# Variometer.net
KiCad netlist of a schematic drawn in EAGLE
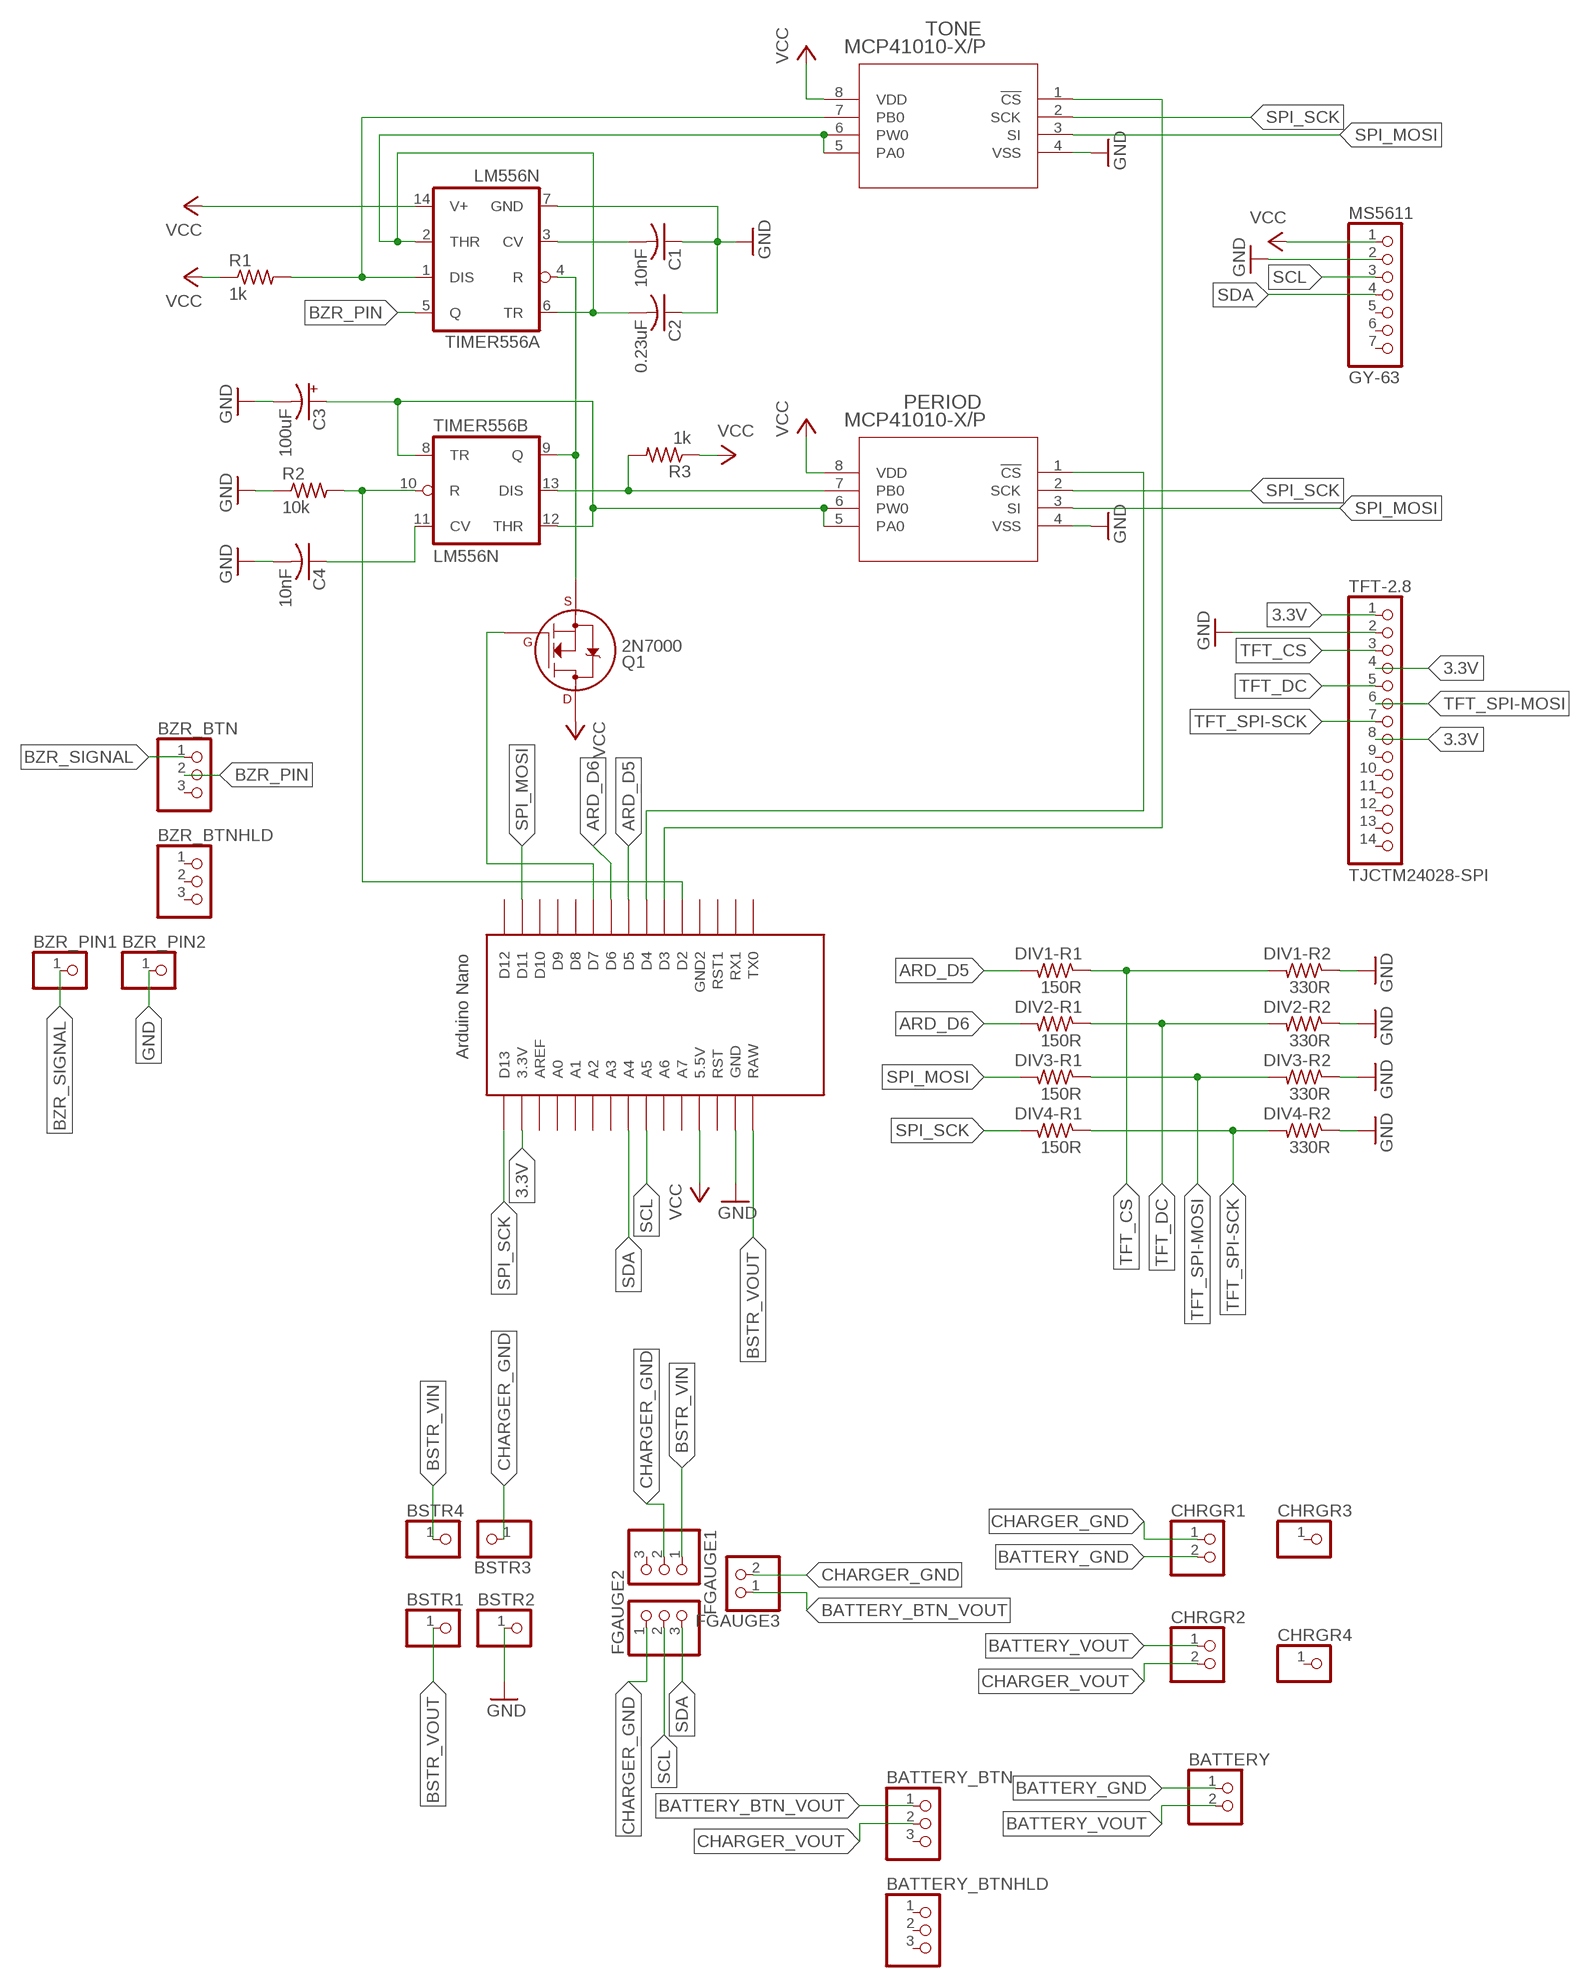
[diagram p0: schematic, sheet 1]

(export (version "E")
  (design (tool "Eeschema 10.0.6"))
  (components
    (comp (ref "BATTERY")
      (value "PINHD-1X2")
      (footprint "eagle-import:1X02")
      (libsource (lib "eagle-import") (part "PINHD-1X2"))
    )
    (comp (ref "BATTERY_BTN")
      (value "PINHD-1X3")
      (footprint "eagle-import:1X03")
      (libsource (lib "eagle-import") (part "PINHD-1X3"))
    )
    (comp (ref "BATTERY_BTNHLD")
      (value "PINHD-1X3")
      (footprint "eagle-import:1X03")
      (libsource (lib "eagle-import") (part "PINHD-1X3"))
    )
    (comp (ref "BSTR1")
      (value "PINHD-1X1")
      (footprint "eagle-import:1X01")
      (libsource (lib "eagle-import") (part "PINHD-1X1"))
    )
    (comp (ref "BSTR2")
      (value "PINHD-1X1")
      (footprint "eagle-import:1X01")
      (libsource (lib "eagle-import") (part "PINHD-1X1"))
    )
    (comp (ref "BSTR3")
      (value "PINHD-1X1")
      (footprint "eagle-import:1X01")
      (libsource (lib "eagle-import") (part "PINHD-1X1"))
    )
    (comp (ref "BSTR4")
      (value "PINHD-1X1")
      (footprint "eagle-import:1X01")
      (libsource (lib "eagle-import") (part "PINHD-1X1"))
    )
    (comp (ref "BZR_BTN")
      (value "PINHD-1X3")
      (footprint "eagle-import:1X03")
      (libsource (lib "eagle-import") (part "PINHD-1X3"))
    )
    (comp (ref "BZR_BTNHLD")
      (value "PINHD-1X3")
      (footprint "eagle-import:1X03")
      (libsource (lib "eagle-import") (part "PINHD-1X3"))
    )
    (comp (ref "BZR_PIN1")
      (value "PINHD-1X1")
      (footprint "eagle-import:1X01")
      (libsource (lib "eagle-import") (part "PINHD-1X1"))
    )
    (comp (ref "BZR_PIN2")
      (value "PINHD-1X1")
      (footprint "eagle-import:1X01")
      (libsource (lib "eagle-import") (part "PINHD-1X1"))
    )
    (comp (ref "C1")
      (value "10nF")
      (footprint "eagle-import:C025-024X044")
      (libsource (lib "eagle-import") (part "C-US025-024X044"))
    )
    (comp (ref "C2")
      (value "0.23uF")
      (footprint "eagle-import:C050-025X075")
      (libsource (lib "eagle-import") (part "C-US050-025X075"))
    )
    (comp (ref "C3")
      (value "100uF")
      (footprint "eagle-import:E2,5-7")
      (libsource (lib "eagle-import") (part "CPOL-USE2.5-7"))
    )
    (comp (ref "C4")
      (value "10nF")
      (footprint "eagle-import:C025-024X044")
      (libsource (lib "eagle-import") (part "C-US025-024X044"))
    )
    (comp (ref "CHRGR1")
      (value "PINHD-1X2")
      (footprint "eagle-import:1X02")
      (libsource (lib "eagle-import") (part "PINHD-1X2"))
    )
    (comp (ref "CHRGR2")
      (value "PINHD-1X2")
      (footprint "eagle-import:1X02")
      (libsource (lib "eagle-import") (part "PINHD-1X2"))
    )
    (comp (ref "CHRGR3")
      (value "PINHD-1X1")
      (footprint "eagle-import:1X01")
      (libsource (lib "eagle-import") (part "PINHD-1X1"))
    )
    (comp (ref "CHRGR4")
      (value "PINHD-1X1")
      (footprint "eagle-import:1X01")
      (libsource (lib "eagle-import") (part "PINHD-1X1"))
    )
    (comp (ref "DIV1-R1")
      (value "150R")
      (footprint "eagle-import:R0805")
      (libsource (lib "eagle-import") (part "R-US_R0805"))
    )
    (comp (ref "DIV1-R2")
      (value "330R")
      (footprint "eagle-import:R0805")
      (libsource (lib "eagle-import") (part "R-US_R0805"))
    )
    (comp (ref "DIV2-R1")
      (value "150R")
      (footprint "eagle-import:R0805")
      (libsource (lib "eagle-import") (part "R-US_R0805"))
    )
    (comp (ref "DIV2-R2")
      (value "330R")
      (footprint "eagle-import:R0805")
      (libsource (lib "eagle-import") (part "R-US_R0805"))
    )
    (comp (ref "DIV3-R1")
      (value "150R")
      (footprint "eagle-import:R0805")
      (libsource (lib "eagle-import") (part "R-US_R0805"))
    )
    (comp (ref "DIV3-R2")
      (value "330R")
      (footprint "eagle-import:R0805")
      (libsource (lib "eagle-import") (part "R-US_R0805"))
    )
    (comp (ref "DIV4-R1")
      (value "150R")
      (footprint "eagle-import:R0805")
      (libsource (lib "eagle-import") (part "R-US_R0805"))
    )
    (comp (ref "DIV4-R2")
      (value "330R")
      (footprint "eagle-import:R0805")
      (libsource (lib "eagle-import") (part "R-US_R0805"))
    )
    (comp (ref "FGAUGE1")
      (value "PINHD-1X3")
      (footprint "eagle-import:1X03")
      (libsource (lib "eagle-import") (part "PINHD-1X3"))
    )
    (comp (ref "FGAUGE2")
      (value "PINHD-1X3")
      (footprint "eagle-import:1X03")
      (libsource (lib "eagle-import") (part "PINHD-1X3"))
    )
    (comp (ref "FGAUGE3")
      (value "PINHD-1X2")
      (footprint "eagle-import:1X02")
      (libsource (lib "eagle-import") (part "PINHD-1X2"))
    )
    (comp (ref "MS5611")
      (value "GY-63")
      (footprint "eagle-import:1X07")
      (libsource (lib "eagle-import") (part "PINHD-1X7"))
    )
    (comp (ref "PERIOD")
      (value "MCP41010-X/P")
      (footprint "eagle-import:PDIP8_300MC")
      (libsource (lib "eagle-import") (part "MCP41010-X/P"))
    )
    (comp (ref "Q1")
      (value "2N7000")
      (footprint "eagle-import:TO-92")
      (libsource (lib "eagle-import") (part "2N700_TO920"))
    )
    (comp (ref "R1")
      (value "1k")
      (footprint "eagle-import:R0805")
      (libsource (lib "eagle-import") (part "R-US_R0805"))
    )
    (comp (ref "R2")
      (value "10k")
      (footprint "eagle-import:R0805")
      (libsource (lib "eagle-import") (part "R-US_R0805"))
    )
    (comp (ref "R3")
      (value "1k")
      (footprint "eagle-import:R0805")
      (libsource (lib "eagle-import") (part "R-US_R0805"))
    )
    (comp (ref "TFT-2.8")
      (value "TJCTM24028-SPI")
      (footprint "eagle-import:1X14")
      (libsource (lib "eagle-import") (part "PINHD-1X14"))
    )
    (comp (ref "TIMER556")
      (value "LM556N")
      (footprint "eagle-import:DIL14")
      (libsource (lib "eagle-import") (part "556NLM"))
    )
    (comp (ref "TONE")
      (value "MCP41010-X/P")
      (footprint "eagle-import:PDIP8_300MC")
      (libsource (lib "eagle-import") (part "MCP41010-X/P"))
    )
    (comp (ref "U$1")
      (value "NANO")
      (footprint "eagle-import:NANO")
      (libsource (lib "eagle-import") (part "NANO"))
    )
  )
  (nets
    (net (code "1") (name "3.3V") (class "Default")
      (node (ref "TFT-2.8") (pin "1") (pinfunction "1_1") (pintype "passive"))
      (node (ref "TFT-2.8") (pin "4") (pinfunction "4_4") (pintype "passive"))
      (node (ref "TFT-2.8") (pin "8") (pinfunction "8_8") (pintype "passive"))
      (node (ref "U$1") (pin "3.3V") (pinfunction "3.3V_3.3V") (pintype "bidirectional"))
    )
    (net (code "2") (name "ARD_D5") (class "Default")
      (node (ref "DIV1-R1") (pin "2") (pinfunction "2_2") (pintype "passive"))
      (node (ref "U$1") (pin "D5") (pinfunction "D5_D5") (pintype "bidirectional"))
    )
    (net (code "3") (name "ARD_D6") (class "Default")
      (node (ref "DIV2-R1") (pin "2") (pinfunction "2_2") (pintype "passive"))
      (node (ref "U$1") (pin "D6") (pinfunction "D6_D6") (pintype "bidirectional"))
    )
    (net (code "4") (name "BATTERY_BTN_VOUT") (class "Default")
      (node (ref "BATTERY_BTN") (pin "1") (pinfunction "1_1") (pintype "passive"))
      (node (ref "FGAUGE3") (pin "1") (pinfunction "1_1") (pintype "passive"))
    )
    (net (code "5") (name "BATTERY_GND") (class "Default")
      (node (ref "BATTERY") (pin "1") (pinfunction "1_1") (pintype "passive"))
      (node (ref "CHRGR1") (pin "2") (pinfunction "2_2") (pintype "passive"))
    )
    (net (code "6") (name "BATTERY_VOUT") (class "Default")
      (node (ref "BATTERY") (pin "2") (pinfunction "2_2") (pintype "passive"))
      (node (ref "CHRGR2") (pin "1") (pinfunction "1_1") (pintype "passive"))
    )
    (net (code "7") (name "BSTR_VIN") (class "Default")
      (node (ref "BSTR4") (pin "1") (pinfunction "1_1") (pintype "passive"))
      (node (ref "FGAUGE1") (pin "1") (pinfunction "1_1") (pintype "passive"))
    )
    (net (code "8") (name "BSTR_VOUT") (class "Default")
      (node (ref "BSTR1") (pin "1") (pinfunction "1_1") (pintype "passive"))
      (node (ref "U$1") (pin "RAW") (pinfunction "RAW_RAW") (pintype "bidirectional"))
    )
    (net (code "9") (name "BZR_PIN") (class "Default")
      (node (ref "BZR_BTN") (pin "2") (pinfunction "2_2") (pintype "passive"))
      (node (ref "TIMER556") (pin "5") (pinfunction "Q_5") (pintype "output"))
    )
    (net (code "10") (name "BZR_SIGNAL") (class "Default")
      (node (ref "BZR_BTN") (pin "1") (pinfunction "1_1") (pintype "passive"))
      (node (ref "BZR_PIN1") (pin "1") (pinfunction "1_1") (pintype "passive"))
    )
    (net (code "11") (name "CHARGER_GND") (class "Default")
      (node (ref "BSTR3") (pin "1") (pinfunction "1_1") (pintype "passive"))
      (node (ref "CHRGR1") (pin "1") (pinfunction "1_1") (pintype "passive"))
      (node (ref "FGAUGE1") (pin "2") (pinfunction "2_2") (pintype "passive"))
      (node (ref "FGAUGE2") (pin "1") (pinfunction "1_1") (pintype "passive"))
      (node (ref "FGAUGE3") (pin "2") (pinfunction "2_2") (pintype "passive"))
    )
    (net (code "12") (name "CHARGER_VOUT") (class "Default")
      (node (ref "BATTERY_BTN") (pin "2") (pinfunction "2_2") (pintype "passive"))
      (node (ref "CHRGR2") (pin "2") (pinfunction "2_2") (pintype "passive"))
    )
    (net (code "13") (name "GND") (class "Default")
      (node (ref "BSTR2") (pin "1") (pinfunction "1_1") (pintype "passive"))
      (node (ref "BZR_PIN2") (pin "1") (pinfunction "1_1") (pintype "passive"))
      (node (ref "C1") (pin "1") (pinfunction "1_1") (pintype "passive"))
      (node (ref "C2") (pin "1") (pinfunction "1_1") (pintype "passive"))
      (node (ref "C3") (pin "-") (pinfunction "-_-") (pintype "passive"))
      (node (ref "C4") (pin "2") (pinfunction "2_2") (pintype "passive"))
      (node (ref "DIV1-R2") (pin "1") (pinfunction "1_1") (pintype "passive"))
      (node (ref "DIV2-R2") (pin "1") (pinfunction "1_1") (pintype "passive"))
      (node (ref "DIV3-R2") (pin "1") (pinfunction "1_1") (pintype "passive"))
      (node (ref "DIV4-R2") (pin "1") (pinfunction "1_1") (pintype "passive"))
      (node (ref "MS5611") (pin "2") (pinfunction "2_2") (pintype "passive"))
      (node (ref "PERIOD") (pin "4") (pinfunction "VSS_4") (pintype "passive"))
      (node (ref "R2") (pin "1") (pinfunction "1_1") (pintype "passive"))
      (node (ref "TFT-2.8") (pin "2") (pinfunction "2_2") (pintype "passive"))
      (node (ref "TIMER556") (pin "7") (pinfunction "GND_7") (pintype "power_in"))
      (node (ref "TONE") (pin "4") (pinfunction "VSS_4") (pintype "passive"))
      (node (ref "U$1") (pin "GND") (pinfunction "GND_GND") (pintype "bidirectional"))
    )
    (net (code "14") (name "Net-(PERIOD-PA0)") (class "Default")
      (node (ref "C3") (pin "+") (pinfunction "+_+") (pintype "passive"))
      (node (ref "PERIOD") (pin "5") (pinfunction "PA0_5") (pintype "passive"))
      (node (ref "PERIOD") (pin "6") (pinfunction "PW0_6") (pintype "passive"))
      (node (ref "TIMER556") (pin "12") (pinfunction "THR_12") (pintype "input"))
      (node (ref "TIMER556") (pin "8") (pinfunction "TR_8") (pintype "input"))
    )
    (net (code "15") (name "Net-(PERIOD-PB0)") (class "Default")
      (node (ref "PERIOD") (pin "7") (pinfunction "PB0_7") (pintype "passive"))
      (node (ref "R3") (pin "2") (pinfunction "2_2") (pintype "passive"))
      (node (ref "TIMER556") (pin "13") (pinfunction "DIS_13") (pintype "input"))
    )
    (net (code "16") (name "Net-(PERIOD-~{CS})") (class "Default")
      (node (ref "PERIOD") (pin "1") (pinfunction "~{CS}_1") (pintype "passive"))
      (node (ref "U$1") (pin "D4") (pinfunction "D4_D4") (pintype "bidirectional"))
    )
    (net (code "17") (name "Net-(Q1-G)") (class "Default")
      (node (ref "Q1") (pin "2") (pinfunction "G_2") (pintype "tri_state"))
      (node (ref "U$1") (pin "D7") (pinfunction "D7_D7") (pintype "bidirectional"))
    )
    (net (code "18") (name "Net-(Q1-S)") (class "Default")
      (node (ref "Q1") (pin "1") (pinfunction "S_1") (pintype "bidirectional"))
      (node (ref "TIMER556") (pin "4") (pinfunction "R_4") (pintype "input"))
      (node (ref "TIMER556") (pin "9") (pinfunction "Q_9") (pintype "output"))
    )
    (net (code "19") (name "Net-(TIMER556A-CV)") (class "Default")
      (node (ref "C1") (pin "2") (pinfunction "2_2") (pintype "passive"))
      (node (ref "TIMER556") (pin "3") (pinfunction "CV_3") (pintype "input"))
    )
    (net (code "20") (name "Net-(TIMER556A-DIS)") (class "Default")
      (node (ref "R1") (pin "2") (pinfunction "2_2") (pintype "passive"))
      (node (ref "TIMER556") (pin "1") (pinfunction "DIS_1") (pintype "input"))
      (node (ref "TONE") (pin "7") (pinfunction "PB0_7") (pintype "passive"))
    )
    (net (code "21") (name "Net-(TIMER556A-THR)") (class "Default")
      (node (ref "C2") (pin "2") (pinfunction "2_2") (pintype "passive"))
      (node (ref "TIMER556") (pin "2") (pinfunction "THR_2") (pintype "input"))
      (node (ref "TIMER556") (pin "6") (pinfunction "TR_6") (pintype "input"))
      (node (ref "TONE") (pin "5") (pinfunction "PA0_5") (pintype "passive"))
      (node (ref "TONE") (pin "6") (pinfunction "PW0_6") (pintype "passive"))
    )
    (net (code "22") (name "Net-(TIMER556B-CV)") (class "Default")
      (node (ref "C4") (pin "1") (pinfunction "1_1") (pintype "passive"))
      (node (ref "TIMER556") (pin "11") (pinfunction "CV_11") (pintype "input"))
    )
    (net (code "23") (name "Net-(TIMER556B-R)") (class "Default")
      (node (ref "R2") (pin "2") (pinfunction "2_2") (pintype "passive"))
      (node (ref "TIMER556") (pin "10") (pinfunction "R_10") (pintype "input"))
      (node (ref "U$1") (pin "D2") (pinfunction "D2_D2") (pintype "bidirectional"))
    )
    (net (code "24") (name "Net-(TONE-~{CS})") (class "Default")
      (node (ref "TONE") (pin "1") (pinfunction "~{CS}_1") (pintype "passive"))
      (node (ref "U$1") (pin "D3") (pinfunction "D3_D3") (pintype "bidirectional"))
    )
    (net (code "25") (name "SCL") (class "Default")
      (node (ref "FGAUGE2") (pin "2") (pinfunction "2_2") (pintype "passive"))
      (node (ref "MS5611") (pin "3") (pinfunction "3_3") (pintype "passive"))
      (node (ref "U$1") (pin "A5") (pinfunction "A5_A5") (pintype "bidirectional"))
    )
    (net (code "26") (name "SDA") (class "Default")
      (node (ref "FGAUGE2") (pin "3") (pinfunction "3_3") (pintype "passive"))
      (node (ref "MS5611") (pin "4") (pinfunction "4_4") (pintype "passive"))
      (node (ref "U$1") (pin "A4") (pinfunction "A4_A4") (pintype "bidirectional"))
    )
    (net (code "27") (name "SPI_MOSI") (class "Default")
      (node (ref "DIV3-R1") (pin "2") (pinfunction "2_2") (pintype "passive"))
      (node (ref "PERIOD") (pin "3") (pinfunction "SI_3") (pintype "passive"))
      (node (ref "TONE") (pin "3") (pinfunction "SI_3") (pintype "passive"))
      (node (ref "U$1") (pin "D11") (pinfunction "D11_D11") (pintype "bidirectional"))
    )
    (net (code "28") (name "SPI_SCK") (class "Default")
      (node (ref "DIV4-R1") (pin "2") (pinfunction "2_2") (pintype "passive"))
      (node (ref "PERIOD") (pin "2") (pinfunction "SCK_2") (pintype "passive"))
      (node (ref "TONE") (pin "2") (pinfunction "SCK_2") (pintype "passive"))
      (node (ref "U$1") (pin "D13") (pinfunction "D13_D13") (pintype "bidirectional"))
    )
    (net (code "29") (name "TFT_CS") (class "Default")
      (node (ref "DIV1-R1") (pin "1") (pinfunction "1_1") (pintype "passive"))
      (node (ref "DIV1-R2") (pin "2") (pinfunction "2_2") (pintype "passive"))
      (node (ref "TFT-2.8") (pin "3") (pinfunction "3_3") (pintype "passive"))
    )
    (net (code "30") (name "TFT_DC") (class "Default")
      (node (ref "DIV2-R1") (pin "1") (pinfunction "1_1") (pintype "passive"))
      (node (ref "DIV2-R2") (pin "2") (pinfunction "2_2") (pintype "passive"))
      (node (ref "TFT-2.8") (pin "5") (pinfunction "5_5") (pintype "passive"))
    )
    (net (code "31") (name "TFT_SPI-MOSI") (class "Default")
      (node (ref "DIV3-R1") (pin "1") (pinfunction "1_1") (pintype "passive"))
      (node (ref "DIV3-R2") (pin "2") (pinfunction "2_2") (pintype "passive"))
      (node (ref "TFT-2.8") (pin "6") (pinfunction "6_6") (pintype "passive"))
    )
    (net (code "32") (name "TFT_SPI-SCK") (class "Default")
      (node (ref "DIV4-R1") (pin "1") (pinfunction "1_1") (pintype "passive"))
      (node (ref "DIV4-R2") (pin "2") (pinfunction "2_2") (pintype "passive"))
      (node (ref "TFT-2.8") (pin "7") (pinfunction "7_7") (pintype "passive"))
    )
    (net (code "33") (name "VCC") (class "Default")
      (node (ref "MS5611") (pin "1") (pinfunction "1_1") (pintype "passive"))
      (node (ref "PERIOD") (pin "8") (pinfunction "VDD_8") (pintype "passive"))
      (node (ref "Q1") (pin "3") (pinfunction "D_3") (pintype "bidirectional"))
      (node (ref "R1") (pin "1") (pinfunction "1_1") (pintype "passive"))
      (node (ref "R3") (pin "1") (pinfunction "1_1") (pintype "passive"))
      (node (ref "TIMER556") (pin "14") (pinfunction "V+_14") (pintype "power_in"))
      (node (ref "TONE") (pin "8") (pinfunction "VDD_8") (pintype "passive"))
      (node (ref "U$1") (pin "5V") (pinfunction "5.5V_5V") (pintype "bidirectional"))
    )
    (net (code "34") (name "unconnected-(BATTERY_BTN-Pad3)") (class "Default")
      (node (ref "BATTERY_BTN") (pin "3") (pinfunction "3_3") (pintype "passive"))
    )
    (net (code "35") (name "unconnected-(BATTERY_BTNHLD-Pad1)") (class "Default")
      (node (ref "BATTERY_BTNHLD") (pin "1") (pinfunction "1_1") (pintype "passive"))
    )
    (net (code "36") (name "unconnected-(BATTERY_BTNHLD-Pad2)") (class "Default")
      (node (ref "BATTERY_BTNHLD") (pin "2") (pinfunction "2_2") (pintype "passive"))
    )
    (net (code "37") (name "unconnected-(BATTERY_BTNHLD-Pad3)") (class "Default")
      (node (ref "BATTERY_BTNHLD") (pin "3") (pinfunction "3_3") (pintype "passive"))
    )
    (net (code "38") (name "unconnected-(BZR_BTN-Pad3)") (class "Default")
      (node (ref "BZR_BTN") (pin "3") (pinfunction "3_3") (pintype "passive"))
    )
    (net (code "39") (name "unconnected-(BZR_BTNHLD-Pad1)") (class "Default")
      (node (ref "BZR_BTNHLD") (pin "1") (pinfunction "1_1") (pintype "passive"))
    )
    (net (code "40") (name "unconnected-(BZR_BTNHLD-Pad2)") (class "Default")
      (node (ref "BZR_BTNHLD") (pin "2") (pinfunction "2_2") (pintype "passive"))
    )
    (net (code "41") (name "unconnected-(BZR_BTNHLD-Pad3)") (class "Default")
      (node (ref "BZR_BTNHLD") (pin "3") (pinfunction "3_3") (pintype "passive"))
    )
    (net (code "42") (name "unconnected-(CHRGR3-Pad1)") (class "Default")
      (node (ref "CHRGR3") (pin "1") (pinfunction "1_1") (pintype "passive"))
    )
    (net (code "43") (name "unconnected-(CHRGR4-Pad1)") (class "Default")
      (node (ref "CHRGR4") (pin "1") (pinfunction "1_1") (pintype "passive"))
    )
    (net (code "44") (name "unconnected-(FGAUGE1-Pad3)") (class "Default")
      (node (ref "FGAUGE1") (pin "3") (pinfunction "3_3") (pintype "passive"))
    )
    (net (code "45") (name "unconnected-(MS5611-Pad5)") (class "Default")
      (node (ref "MS5611") (pin "5") (pinfunction "5_5") (pintype "passive"))
    )
    (net (code "46") (name "unconnected-(MS5611-Pad6)") (class "Default")
      (node (ref "MS5611") (pin "6") (pinfunction "6_6") (pintype "passive"))
    )
    (net (code "47") (name "unconnected-(MS5611-Pad7)") (class "Default")
      (node (ref "MS5611") (pin "7") (pinfunction "7_7") (pintype "passive"))
    )
    (net (code "48") (name "unconnected-(TFT-2.8-Pad9)") (class "Default")
      (node (ref "TFT-2.8") (pin "9") (pinfunction "9_9") (pintype "passive"))
    )
    (net (code "49") (name "unconnected-(TFT-2.8-Pad10)") (class "Default")
      (node (ref "TFT-2.8") (pin "10") (pinfunction "10_10") (pintype "passive"))
    )
    (net (code "50") (name "unconnected-(TFT-2.8-Pad11)") (class "Default")
      (node (ref "TFT-2.8") (pin "11") (pinfunction "11_11") (pintype "passive"))
    )
    (net (code "51") (name "unconnected-(TFT-2.8-Pad12)") (class "Default")
      (node (ref "TFT-2.8") (pin "12") (pinfunction "12_12") (pintype "passive"))
    )
    (net (code "52") (name "unconnected-(TFT-2.8-Pad13)") (class "Default")
      (node (ref "TFT-2.8") (pin "13") (pinfunction "13_13") (pintype "passive"))
    )
    (net (code "53") (name "unconnected-(TFT-2.8-Pad14)") (class "Default")
      (node (ref "TFT-2.8") (pin "14") (pinfunction "14_14") (pintype "passive"))
    )
    (net (code "54") (name "unconnected-(U$1-GND2-PadGND1)") (class "Default")
      (node (ref "U$1") (pin "GND1") (pinfunction "GND2_GND1") (pintype "bidirectional"))
    )
    (net (code "55") (name "unconnected-(U$1-PadA0)") (class "Default")
      (node (ref "U$1") (pin "A0") (pinfunction "A0_A0") (pintype "bidirectional"))
    )
    (net (code "56") (name "unconnected-(U$1-PadA1)") (class "Default")
      (node (ref "U$1") (pin "A1") (pinfunction "A1_A1") (pintype "bidirectional"))
    )
    (net (code "57") (name "unconnected-(U$1-PadA2)") (class "Default")
      (node (ref "U$1") (pin "A2") (pinfunction "A2_A2") (pintype "bidirectional"))
    )
    (net (code "58") (name "unconnected-(U$1-PadA3)") (class "Default")
      (node (ref "U$1") (pin "A3") (pinfunction "A3_A3") (pintype "bidirectional"))
    )
    (net (code "59") (name "unconnected-(U$1-PadA6)") (class "Default")
      (node (ref "U$1") (pin "A6") (pinfunction "A6_A6") (pintype "bidirectional"))
    )
    (net (code "60") (name "unconnected-(U$1-PadA7)") (class "Default")
      (node (ref "U$1") (pin "A7") (pinfunction "A7_A7") (pintype "bidirectional"))
    )
    (net (code "61") (name "unconnected-(U$1-PadAREF)") (class "Default")
      (node (ref "U$1") (pin "AREF") (pinfunction "AREF_AREF") (pintype "bidirectional"))
    )
    (net (code "62") (name "unconnected-(U$1-PadD8)") (class "Default")
      (node (ref "U$1") (pin "D8") (pinfunction "D8_D8") (pintype "bidirectional"))
    )
    (net (code "63") (name "unconnected-(U$1-PadD9)") (class "Default")
      (node (ref "U$1") (pin "D9") (pinfunction "D9_D9") (pintype "bidirectional"))
    )
    (net (code "64") (name "unconnected-(U$1-PadD10)") (class "Default")
      (node (ref "U$1") (pin "D10") (pinfunction "D10_D10") (pintype "bidirectional"))
    )
    (net (code "65") (name "unconnected-(U$1-PadD12)") (class "Default")
      (node (ref "U$1") (pin "D12") (pinfunction "D12_D12") (pintype "bidirectional"))
    )
    (net (code "66") (name "unconnected-(U$1-PadICSP1)") (class "Default")
      (node (ref "U$1") (pin "ICSP1") (pinfunction "ICSP1_ICSP1") (pintype "bidirectional"))
    )
    (net (code "67") (name "unconnected-(U$1-PadICSP2)") (class "Default")
      (node (ref "U$1") (pin "ICSP2") (pinfunction "ICSP2_ICSP2") (pintype "bidirectional"))
    )
    (net (code "68") (name "unconnected-(U$1-PadICSP3)") (class "Default")
      (node (ref "U$1") (pin "ICSP3") (pinfunction "ICSP3_ICSP3") (pintype "bidirectional"))
    )
    (net (code "69") (name "unconnected-(U$1-PadICSP4)") (class "Default")
      (node (ref "U$1") (pin "ICSP4") (pinfunction "ICSP4_ICSP4") (pintype "bidirectional"))
    )
    (net (code "70") (name "unconnected-(U$1-PadICSP5)") (class "Default")
      (node (ref "U$1") (pin "ICSP5") (pinfunction "ICSP5_ICSP5") (pintype "bidirectional"))
    )
    (net (code "71") (name "unconnected-(U$1-PadICSP6)") (class "Default")
      (node (ref "U$1") (pin "ICSP6") (pinfunction "ICSP6_ICSP6") (pintype "bidirectional"))
    )
    (net (code "72") (name "unconnected-(U$1-PadRST)") (class "Default")
      (node (ref "U$1") (pin "RST") (pinfunction "RST_RST") (pintype "bidirectional"))
    )
    (net (code "73") (name "unconnected-(U$1-PadRST1)") (class "Default")
      (node (ref "U$1") (pin "RST1") (pinfunction "RST1_RST1") (pintype "bidirectional"))
    )
    (net (code "74") (name "unconnected-(U$1-PadRX1)") (class "Default")
      (node (ref "U$1") (pin "RX1") (pinfunction "RX1_RX1") (pintype "bidirectional"))
    )
    (net (code "75") (name "unconnected-(U$1-PadTX0)") (class "Default")
      (node (ref "U$1") (pin "TX0") (pinfunction "TX0_TX0") (pintype "bidirectional"))
    )
  )
)
